# MCU.net
KiCad netlist of a schematic drawn in Altium Designer
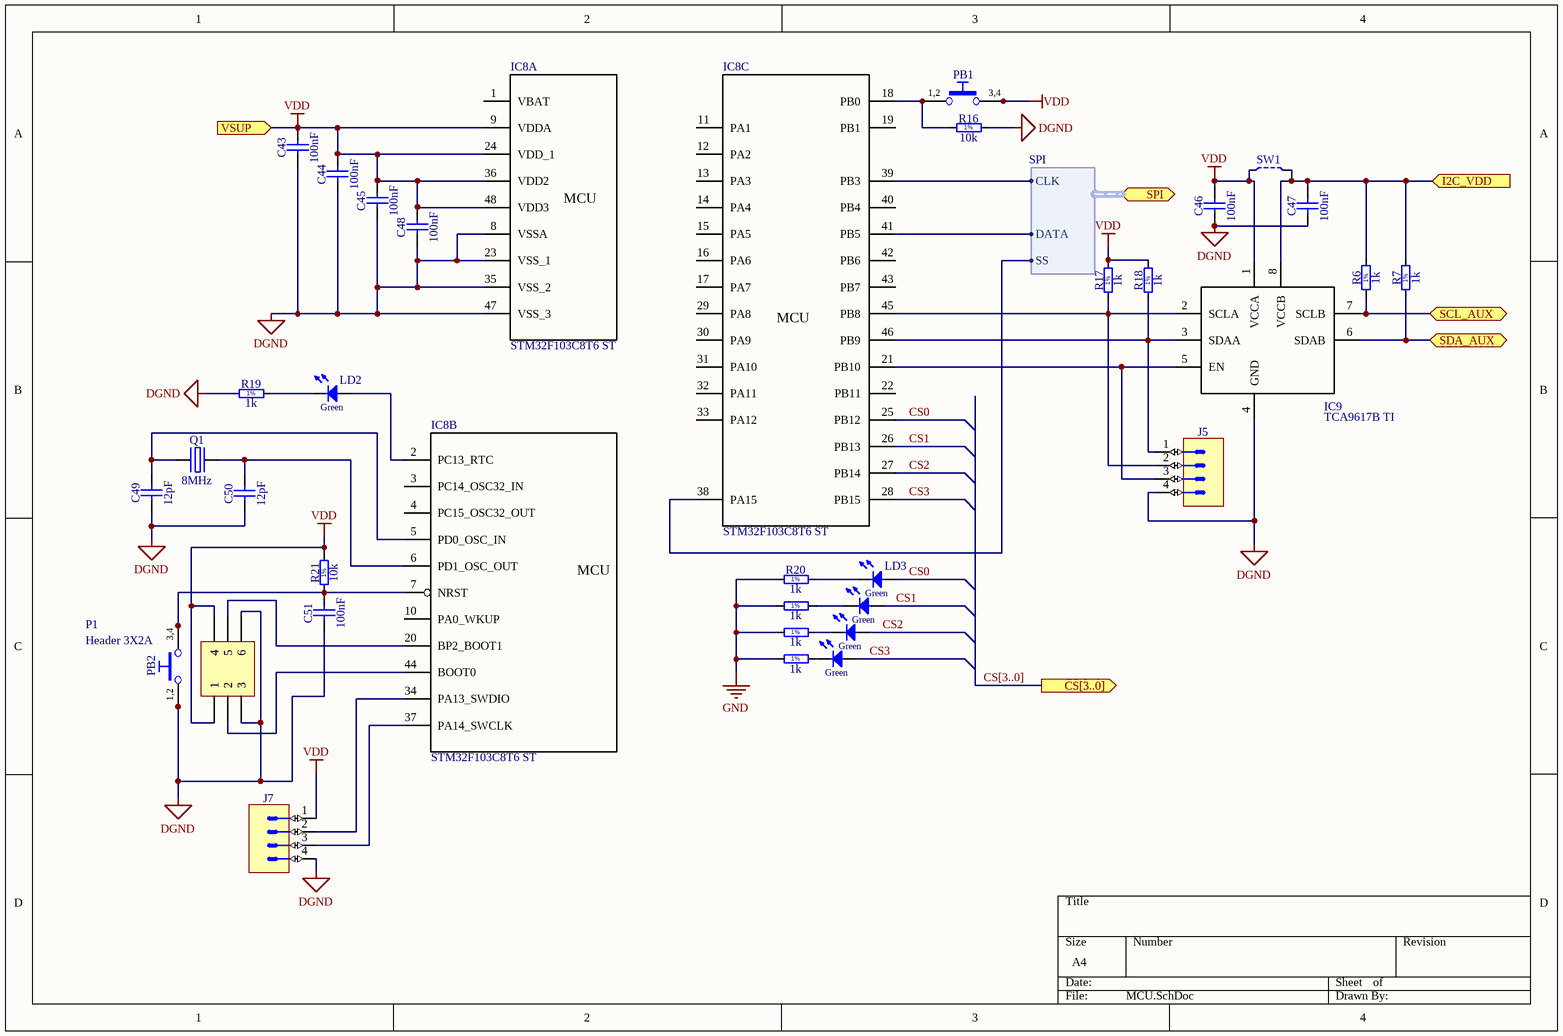
[diagram p0: MCU.SchDoc]

(export (version "E")
  (design (tool "Eeschema 10.0.6"))
  (components
    (comp (ref "C43")
      (value "100nF")
      (footprint "CAPC2012X135N")
      (description "Non-polarised capacitor")
      (fields
        (field (name "PART NUMBER") "CC0805_100NF_50V_10%_X7R")
        (field (name "VOLTAGE") "50V")
        (field (name "AUTHOR") "CERN DEM JLC")
      )
      (libsource (lib "Capacitors") (part "Capacitor - non polarized"))
    )
    (comp (ref "C44")
      (value "100nF")
      (footprint "CAPC2012X135N")
      (description "Non-polarised capacitor")
      (fields
        (field (name "PART NUMBER") "CC0805_100NF_50V_10%_X7R")
        (field (name "VOLTAGE") "50V")
        (field (name "AUTHOR") "CERN DEM JLC")
      )
      (libsource (lib "Capacitors") (part "Capacitor - non polarized"))
    )
    (comp (ref "C45")
      (value "100nF")
      (footprint "CAPC2012X135N")
      (description "Non-polarised capacitor")
      (fields
        (field (name "PART NUMBER") "CC0805_100NF_50V_10%_X7R")
        (field (name "VOLTAGE") "50V")
        (field (name "AUTHOR") "CERN DEM JLC")
      )
      (libsource (lib "Capacitors") (part "Capacitor - non polarized"))
    )
    (comp (ref "C46")
      (value "100nF")
      (footprint "CAPC2012X135N")
      (description "Non-polarised capacitor")
      (fields
        (field (name "PART NUMBER") "CC0805_100NF_50V_10%_X7R")
        (field (name "VOLTAGE") "50V")
        (field (name "AUTHOR") "CERN DEM JLC")
      )
      (libsource (lib "Capacitors") (part "Capacitor - non polarized"))
    )
    (comp (ref "C47")
      (value "100nF")
      (footprint "CAPC2012X135N")
      (description "Non-polarised capacitor")
      (fields
        (field (name "PART NUMBER") "CC0805_100NF_50V_10%_X7R")
        (field (name "VOLTAGE") "50V")
        (field (name "AUTHOR") "CERN DEM JLC")
      )
      (libsource (lib "Capacitors") (part "Capacitor - non polarized"))
    )
    (comp (ref "C48")
      (value "100nF")
      (footprint "CAPC2012X135N")
      (description "Non-polarised capacitor")
      (fields
        (field (name "PART NUMBER") "CC0805_100NF_50V_10%_X7R")
        (field (name "VOLTAGE") "50V")
        (field (name "AUTHOR") "CERN DEM JLC")
      )
      (libsource (lib "Capacitors") (part "Capacitor - non polarized"))
    )
    (comp (ref "C49")
      (value "12pF")
      (footprint "CAPC2012X135N")
      (description "Non-polarised capacitor")
      (fields
        (field (name "PART NUMBER") "CC0805_12PF_50V_5%_NP0")
        (field (name "VOLTAGE") "50V")
        (field (name "AUTHOR") "CERN DEM JLC")
      )
      (libsource (lib "Capacitors") (part "Capacitor - non polarized"))
    )
    (comp (ref "C50")
      (value "12pF")
      (footprint "CAPC2012X135N")
      (description "Non-polarised capacitor")
      (fields
        (field (name "PART NUMBER") "CC0805_12PF_50V_5%_NP0")
        (field (name "VOLTAGE") "50V")
        (field (name "AUTHOR") "CERN DEM JLC")
      )
      (libsource (lib "Capacitors") (part "Capacitor - non polarized"))
    )
    (comp (ref "C51")
      (value "100nF")
      (footprint "CAPC2012X135N")
      (description "Non-polarised capacitor")
      (fields
        (field (name "PART NUMBER") "CC0805_100NF_50V_10%_X7R")
        (field (name "VOLTAGE") "50V")
        (field (name "AUTHOR") "CERN DEM JLC")
      )
      (libsource (lib "Capacitors") (part "Capacitor - non polarized"))
    )
    (comp (ref "IC8")
      (value "STM32F103C8T6 ST")
      (footprint "QFP50P900X900X160-48N")
      (fields (field (name "MANUFACTURER") "ST"))
      (libsource (lib "Additional") (part "STM32F103C8T6"))
    )
    (comp (ref "IC9")
      (value "TCA9617B TI")
      (footprint "TSOP65P490X110-8N")
      (fields (field (name "MANUFACTURER") "TI"))
      (libsource (lib "Additional") (part "TCA9617B"))
    )
    (comp (ref "J5")
      (value "Header 4")
      (footprint "PRECI-DIP_350-V3-104-00-001101")
      (description "Connector 4 Male")
      (fields
        (field (name "PART NUMBER") "PRECI-DIP_350-V3-104-00-001101")
        (field (name "MANUFACTURER") "PRECI-DIP")
        (field (name "AUTHOR") "CERN DEM BC")
      )
      (libsource (lib "") (part "Connector 4 Male_1"))
    )
    (comp (ref "J7")
      (value "Header 4")
      (footprint "PRECI-DIP_350-V3-104-00-001101")
      (description "Connector 4 Male")
      (fields
        (field (name "PART NUMBER") "PRECI-DIP_350-V3-104-00-001101")
        (field (name "MANUFACTURER") "PRECI-DIP")
        (field (name "AUTHOR") "CERN DEM BC")
      )
      (libsource (lib "Connectors") (part "Connector 4 Male"))
    )
    (comp (ref "LD2")
      (value "Green")
      (footprint "LED_OSRAM_LGR971")
      (description "LED Green 1C 2A")
      (fields
        (field (name "PART NUMBER") "LED_OSRAM_LGR971")
        (field (name "MANUFACTURER") "OSRAM")
        (field (name "AUTHOR") "CERN DEM JLC")
      )
      (libsource (lib "ICs And Semiconductors") (part "LED Green 1C 2A"))
    )
    (comp (ref "LD3")
      (value "Green")
      (footprint "LED_OSRAM_LGR971")
      (description "LED Green 1C 2A")
      (fields
        (field (name "PART NUMBER") "LED_OSRAM_LGR971")
        (field (name "MANUFACTURER") "OSRAM")
        (field (name "AUTHOR") "CERN DEM JLC")
      )
      (libsource (lib "ICs And Semiconductors") (part "LED Green 1C 2A"))
    )
    (comp (ref "LD4")
      (value "Green")
      (footprint "LED_OSRAM_LGR971")
      (description "LED Green 1C 2A")
      (fields
        (field (name "PART NUMBER") "LED_OSRAM_LGR971")
        (field (name "MANUFACTURER") "OSRAM")
        (field (name "AUTHOR") "CERN DEM JLC")
      )
      (libsource (lib "ICs And Semiconductors") (part "LED Green 1C 2A"))
    )
    (comp (ref "LD5")
      (value "Green")
      (footprint "LED_OSRAM_LGR971")
      (description "LED Green 1C 2A")
      (fields
        (field (name "PART NUMBER") "LED_OSRAM_LGR971")
        (field (name "MANUFACTURER") "OSRAM")
        (field (name "AUTHOR") "CERN DEM JLC")
      )
      (libsource (lib "ICs And Semiconductors") (part "LED Green 1C 2A"))
    )
    (comp (ref "LD6")
      (value "Green")
      (footprint "LED_OSRAM_LGR971")
      (description "LED Green 1C 2A")
      (fields
        (field (name "PART NUMBER") "LED_OSRAM_LGR971")
        (field (name "MANUFACTURER") "OSRAM")
        (field (name "AUTHOR") "CERN DEM JLC")
      )
      (libsource (lib "ICs And Semiconductors") (part "LED Green 1C 2A"))
    )
    (comp (ref "P1")
      (value "Header 3X2A")
      (footprint "HDR2X3_CEN")
      (description "Header, 3-Pin, Dual row")
      (fields (field (name "PUBLISHER") "Altium Limited"))
      (libsource (lib "Miscellaneous Connectors") (part "Header 3X2A"))
    )
    (comp (ref "PB1")
      (value "Push Button")
      (footprint "PB_OMRON_B3F-1000")
      (description "Push-Button Switch SPDT")
      (fields
        (field (name "PART NUMBER") "PB_OMRON_B3F-1000")
        (field (name "MANUFACTURER") "OMRON")
        (field (name "AUTHOR") "CERN DEM JMW")
      )
      (libsource (lib "") (part "PB SPST 12NO-34NO_1"))
    )
    (comp (ref "PB2")
      (value "Push Button")
      (footprint "PB_OMRON_B3F-1000")
      (description "Push-Button Switch SPDT")
      (fields
        (field (name "PART NUMBER") "PB_OMRON_B3F-1000")
        (field (name "MANUFACTURER") "OMRON")
        (field (name "AUTHOR") "CERN DEM JMW")
      )
      (libsource (lib "Eletro-mechanical") (part "PB SPST 12NO-34NO"))
    )
    (comp (ref "Q1")
      (value "8MHz")
      (footprint "XTAL_TXC_7A")
      (description "Quartz Crystal")
      (fields
        (field (name "PART NUMBER") "XTAL_8MHZ_TXC_7A-8.000MAAE-T")
        (field (name "MANUFACTURER") "TXC CORPORATION")
        (field (name "AUTHOR") "CERN DEM JLC")
      )
      (libsource (lib "ICs And Semiconductors") (part "Quartz Crystal"))
    )
    (comp (ref "R6")
      (value "1k")
      (footprint "RESC2012X60N")
      (description "Resistor - 1%")
      (fields
        (field (name "PART NUMBER") "R0805_1K_1%_0.125W_100PPM")
        (field (name "POWER") "0.125W")
        (field (name "AUTHOR") "CERN DEM JLC")
      )
      (libsource (lib "Resistors") (part "Resistor - 1%"))
    )
    (comp (ref "R7")
      (value "1k")
      (footprint "RESC2012X60N")
      (description "Resistor - 1%")
      (fields
        (field (name "PART NUMBER") "R0805_1K_1%_0.125W_100PPM")
        (field (name "POWER") "0.125W")
        (field (name "AUTHOR") "CERN DEM JLC")
      )
      (libsource (lib "Resistors") (part "Resistor - 1%"))
    )
    (comp (ref "R16")
      (value "10k")
      (footprint "RESC2012X60N")
      (description "Resistor - 1%")
      (fields
        (field (name "PART NUMBER") "R0805_10K_1%_0.125W_100PPM")
        (field (name "POWER") "0.125W")
        (field (name "AUTHOR") "CERN DEM JLC")
      )
      (libsource (lib "Resistors") (part "Resistor - 1%"))
    )
    (comp (ref "R17")
      (value "1k")
      (footprint "RESC2012X60N")
      (description "Resistor - 1%")
      (fields
        (field (name "PART NUMBER") "R0805_1K_1%_0.125W_100PPM")
        (field (name "POWER") "0.125W")
        (field (name "AUTHOR") "CERN DEM JLC")
      )
      (libsource (lib "Resistors") (part "Resistor - 1%"))
    )
    (comp (ref "R18")
      (value "1k")
      (footprint "RESC2012X60N")
      (description "Resistor - 1%")
      (fields
        (field (name "PART NUMBER") "R0805_1K_1%_0.125W_100PPM")
        (field (name "POWER") "0.125W")
        (field (name "AUTHOR") "CERN DEM JLC")
      )
      (libsource (lib "Resistors") (part "Resistor - 1%"))
    )
    (comp (ref "R19")
      (value "1k")
      (footprint "RESC2012X60N")
      (description "Resistor - 1%")
      (fields
        (field (name "PART NUMBER") "R0805_1K_1%_0.125W_100PPM")
        (field (name "POWER") "0.125W")
        (field (name "AUTHOR") "CERN DEM JLC")
      )
      (libsource (lib "Resistors") (part "Resistor - 1%"))
    )
    (comp (ref "R20")
      (value "1k")
      (footprint "RESC2012X60N")
      (description "Resistor - 1%")
      (fields
        (field (name "PART NUMBER") "R0805_1K_1%_0.125W_100PPM")
        (field (name "POWER") "0.125W")
        (field (name "AUTHOR") "CERN DEM JLC")
      )
      (libsource (lib "Resistors") (part "Resistor - 1%"))
    )
    (comp (ref "R21")
      (value "10k")
      (footprint "RESC2012X60N")
      (description "Resistor - 1%")
      (fields
        (field (name "PART NUMBER") "R0805_10K_1%_0.125W_100PPM")
        (field (name "POWER") "0.125W")
        (field (name "AUTHOR") "CERN DEM JLC")
      )
      (libsource (lib "Resistors") (part "Resistor - 1%"))
    )
    (comp (ref "R22")
      (value "1k")
      (footprint "RESC2012X60N")
      (description "Resistor - 1%")
      (fields
        (field (name "PART NUMBER") "R0805_1K_1%_0.125W_100PPM")
        (field (name "POWER") "0.125W")
        (field (name "AUTHOR") "CERN DEM JLC")
      )
      (libsource (lib "Resistors") (part "Resistor - 1%"))
    )
    (comp (ref "R23")
      (value "1k")
      (footprint "RESC2012X60N")
      (description "Resistor - 1%")
      (fields
        (field (name "PART NUMBER") "R0805_1K_1%_0.125W_100PPM")
        (field (name "POWER") "0.125W")
        (field (name "AUTHOR") "CERN DEM JLC")
      )
      (libsource (lib "Resistors") (part "Resistor - 1%"))
    )
    (comp (ref "R24")
      (value "1k")
      (footprint "RESC2012X60N")
      (description "Resistor - 1%")
      (fields
        (field (name "PART NUMBER") "R0805_1K_1%_0.125W_100PPM")
        (field (name "POWER") "0.125W")
        (field (name "AUTHOR") "CERN DEM JLC")
      )
      (libsource (lib "Resistors") (part "Resistor - 1%"))
    )
    (comp (ref "SW1")
      (value "Switch")
      (footprint "JUMPSMD0805_G50")
      (description "2 SMD Pads for Bound by Solder  Drop")
      (fields
        (field (name "PART NUMBER") "JUMPSMD0805_G50")
        (field (name "MANUFACTURER") "None")
        (field (name "AUTHOR") "CERN DEM JLC")
      )
      (libsource (lib "Eletro-mechanical") (part "SMD Solder Jumper"))
    )
  )
  (nets
    (net (code "2") (name "/CLK") (class "Default")
      (node (ref "IC8") (pin "39") (pinfunction "PB3_39") (pintype "passive"))
    )
    (net (code "3") (name "/CS0") (class "Default")
      (node (ref "IC8") (pin "25") (pinfunction "PB12_25") (pintype "passive"))
      (node (ref "LD3") (pin "2") (pinfunction "A_2") (pintype "passive"))
    )
    (net (code "4") (name "/CS1") (class "Default")
      (node (ref "IC8") (pin "26") (pinfunction "PB13_26") (pintype "passive"))
      (node (ref "LD4") (pin "2") (pinfunction "A_2") (pintype "passive"))
    )
    (net (code "5") (name "/CS2") (class "Default")
      (node (ref "IC8") (pin "27") (pinfunction "PB14_27") (pintype "passive"))
      (node (ref "LD5") (pin "2") (pinfunction "A_2") (pintype "passive"))
    )
    (net (code "6") (name "/CS3") (class "Default")
      (node (ref "IC8") (pin "28") (pinfunction "PB15_28") (pintype "passive"))
      (node (ref "LD6") (pin "2") (pinfunction "A_2") (pintype "passive"))
    )
    (net (code "8") (name "/DATA") (class "Default")
      (node (ref "IC8") (pin "41") (pinfunction "PB5_41") (pintype "passive"))
    )
    (net (code "9") (name "/I2C_VDD") (class "Default")
      (node (ref "C47") (pin "2") (pinfunction "2_2") (pintype "passive"))
      (node (ref "IC9") (pin "8") (pinfunction "VCCB_8") (pintype "passive"))
      (node (ref "R6") (pin "2") (pinfunction "2_2") (pintype "passive"))
      (node (ref "R7") (pin "2") (pinfunction "2_2") (pintype "passive"))
      (node (ref "SW1") (pin "2") (pinfunction "2_2") (pintype "passive"))
    )
    (net (code "10") (name "/SCL_AUX") (class "Default")
      (node (ref "IC9") (pin "7") (pinfunction "SCLB_7") (pintype "passive"))
      (node (ref "R6") (pin "1") (pinfunction "1_1") (pintype "passive"))
    )
    (net (code "11") (name "/SDA_AUX") (class "Default")
      (node (ref "IC9") (pin "6") (pinfunction "SDAB_6") (pintype "passive"))
      (node (ref "R7") (pin "1") (pinfunction "1_1") (pintype "passive"))
    )
    (net (code "12") (name "/SS") (class "Default")
      (node (ref "IC8") (pin "38") (pinfunction "PA15_38") (pintype "passive"))
    )
    (net (code "14") (name "DGND") (class "Default")
      (node (ref "C43") (pin "1") (pinfunction "1_1") (pintype "passive"))
      (node (ref "C44") (pin "1") (pinfunction "1_1") (pintype "passive"))
      (node (ref "C45") (pin "1") (pinfunction "1_1") (pintype "passive"))
      (node (ref "C46") (pin "1") (pinfunction "1_1") (pintype "passive"))
      (node (ref "C47") (pin "1") (pinfunction "1_1") (pintype "passive"))
      (node (ref "C48") (pin "1") (pinfunction "1_1") (pintype "passive"))
      (node (ref "C49") (pin "1") (pinfunction "1_1") (pintype "passive"))
      (node (ref "C50") (pin "1") (pinfunction "1_1") (pintype "passive"))
      (node (ref "C51") (pin "1") (pinfunction "1_1") (pintype "passive"))
      (node (ref "IC8") (pin "23") (pinfunction "VSS_1_23") (pintype "passive"))
      (node (ref "IC8") (pin "35") (pinfunction "VSS_2_35") (pintype "passive"))
      (node (ref "IC8") (pin "47") (pinfunction "VSS_3_47") (pintype "passive"))
      (node (ref "IC8") (pin "8") (pinfunction "VSSA_8") (pintype "passive"))
      (node (ref "IC9") (pin "4") (pinfunction "GND_4") (pintype "passive"))
      (node (ref "J5") (pin "4") (pinfunction "4_4") (pintype "bidirectional"))
      (node (ref "J7") (pin "4") (pinfunction "4_4") (pintype "bidirectional"))
      (node (ref "P1") (pin "3") (pinfunction "3_3") (pintype "passive"))
      (node (ref "P1") (pin "6") (pinfunction "6_6") (pintype "passive"))
      (node (ref "PB2") (pin "1") (pinfunction "1_1") (pintype "passive"))
      (node (ref "PB2") (pin "2") (pinfunction "2_2") (pintype "passive"))
      (node (ref "R16") (pin "2") (pinfunction "2_2") (pintype "passive"))
      (node (ref "R19") (pin "1") (pinfunction "1_1") (pintype "passive"))
    )
    (net (code "15") (name "GND") (class "Default")
      (node (ref "R20") (pin "1") (pinfunction "1_1") (pintype "passive"))
      (node (ref "R22") (pin "1") (pinfunction "1_1") (pintype "passive"))
      (node (ref "R23") (pin "1") (pinfunction "1_1") (pintype "passive"))
      (node (ref "R24") (pin "1") (pinfunction "1_1") (pintype "passive"))
    )
    (net (code "16") (name "Net-(IC8B-BOOT0)") (class "Default")
      (node (ref "IC8") (pin "44") (pinfunction "BOOT0_44") (pintype "passive"))
      (node (ref "P1") (pin "2") (pinfunction "2_2") (pintype "passive"))
    )
    (net (code "17") (name "Net-(IC8B-BP2_BOOT1)") (class "Default")
      (node (ref "IC8") (pin "20") (pinfunction "BP2_BOOT1_20") (pintype "passive"))
      (node (ref "P1") (pin "5") (pinfunction "5_5") (pintype "passive"))
    )
    (net (code "18") (name "Net-(IC8B-NRST)") (class "Default")
      (node (ref "C51") (pin "2") (pinfunction "2_2") (pintype "passive"))
      (node (ref "IC8") (pin "7") (pinfunction "NRST_7") (pintype "passive"))
      (node (ref "PB2") (pin "3") (pinfunction "3_3") (pintype "passive"))
      (node (ref "PB2") (pin "4") (pinfunction "4_4") (pintype "passive"))
      (node (ref "R21") (pin "1") (pinfunction "1_1") (pintype "passive"))
    )
    (net (code "19") (name "Net-(IC8B-PA13_SWDIO)") (class "Default")
      (node (ref "IC8") (pin "34") (pinfunction "PA13_SWDIO_34") (pintype "passive"))
      (node (ref "J7") (pin "2") (pinfunction "2_2") (pintype "bidirectional"))
    )
    (net (code "20") (name "Net-(IC8B-PA14_SWCLK)") (class "Default")
      (node (ref "IC8") (pin "37") (pinfunction "PA14_SWCLK_37") (pintype "passive"))
      (node (ref "J7") (pin "3") (pinfunction "3_3") (pintype "bidirectional"))
    )
    (net (code "21") (name "Net-(IC8B-PC13_RTC)") (class "Default")
      (node (ref "IC8") (pin "2") (pinfunction "PC13_RTC_2") (pintype "passive"))
      (node (ref "LD2") (pin "2") (pinfunction "A_2") (pintype "passive"))
    )
    (net (code "22") (name "Net-(IC8B-PD0_OSC_IN)") (class "Default")
      (node (ref "C49") (pin "2") (pinfunction "2_2") (pintype "passive"))
      (node (ref "IC8") (pin "5") (pinfunction "PD0_OSC_IN_5") (pintype "passive"))
      (node (ref "Q1") (pin "1") (pinfunction "OSC1_1") (pintype "passive"))
    )
    (net (code "23") (name "Net-(IC8B-PD1_OSC_OUT)") (class "Default")
      (node (ref "C50") (pin "2") (pinfunction "2_2") (pintype "passive"))
      (node (ref "IC8") (pin "6") (pinfunction "PD1_OSC_OUT_6") (pintype "passive"))
      (node (ref "Q1") (pin "2") (pinfunction "OSC2_2") (pintype "passive"))
    )
    (net (code "24") (name "Net-(IC8C-PB0)") (class "Default")
      (node (ref "IC8") (pin "18") (pinfunction "PB0_18") (pintype "passive"))
      (node (ref "PB1") (pin "1") (pinfunction "1_1") (pintype "passive"))
      (node (ref "PB1") (pin "2") (pinfunction "2_2") (pintype "passive"))
      (node (ref "R16") (pin "1") (pinfunction "1_1") (pintype "passive"))
    )
    (net (code "25") (name "Net-(IC8C-PB8)") (class "Default")
      (node (ref "IC8") (pin "45") (pinfunction "PB8_45") (pintype "passive"))
      (node (ref "IC9") (pin "2") (pinfunction "SCLA_2") (pintype "passive"))
      (node (ref "J5") (pin "2") (pinfunction "2_2") (pintype "bidirectional"))
      (node (ref "R17") (pin "1") (pinfunction "1_1") (pintype "passive"))
    )
    (net (code "26") (name "Net-(IC8C-PB9)") (class "Default")
      (node (ref "IC8") (pin "46") (pinfunction "PB9_46") (pintype "passive"))
      (node (ref "IC9") (pin "3") (pinfunction "SDAA_3") (pintype "passive"))
      (node (ref "J5") (pin "1") (pinfunction "1_1") (pintype "bidirectional"))
      (node (ref "R18") (pin "1") (pinfunction "1_1") (pintype "passive"))
    )
    (net (code "27") (name "Net-(IC8C-PB10)") (class "Default")
      (node (ref "IC8") (pin "21") (pinfunction "PB10_21") (pintype "passive"))
      (node (ref "IC9") (pin "5") (pinfunction "EN_5") (pintype "passive"))
      (node (ref "J5") (pin "3") (pinfunction "3_3") (pintype "bidirectional"))
    )
    (net (code "28") (name "Net-(LD2-C)") (class "Default")
      (node (ref "LD2") (pin "1") (pinfunction "C_1") (pintype "passive"))
      (node (ref "R19") (pin "2") (pinfunction "2_2") (pintype "passive"))
    )
    (net (code "29") (name "Net-(LD3-C)") (class "Default")
      (node (ref "LD3") (pin "1") (pinfunction "C_1") (pintype "passive"))
      (node (ref "R20") (pin "2") (pinfunction "2_2") (pintype "passive"))
    )
    (net (code "30") (name "Net-(LD4-C)") (class "Default")
      (node (ref "LD4") (pin "1") (pinfunction "C_1") (pintype "passive"))
      (node (ref "R22") (pin "2") (pinfunction "2_2") (pintype "passive"))
    )
    (net (code "31") (name "Net-(LD5-C)") (class "Default")
      (node (ref "LD5") (pin "1") (pinfunction "C_1") (pintype "passive"))
      (node (ref "R23") (pin "2") (pinfunction "2_2") (pintype "passive"))
    )
    (net (code "32") (name "Net-(LD6-C)") (class "Default")
      (node (ref "LD6") (pin "1") (pinfunction "C_1") (pintype "passive"))
      (node (ref "R24") (pin "2") (pinfunction "2_2") (pintype "passive"))
    )
    (net (code "33") (name "VDD") (class "Default")
      (node (ref "C43") (pin "2") (pinfunction "2_2") (pintype "passive"))
      (node (ref "C44") (pin "2") (pinfunction "2_2") (pintype "passive"))
      (node (ref "C45") (pin "2") (pinfunction "2_2") (pintype "passive"))
      (node (ref "C46") (pin "2") (pinfunction "2_2") (pintype "passive"))
      (node (ref "C48") (pin "2") (pinfunction "2_2") (pintype "passive"))
      (node (ref "IC8") (pin "24") (pinfunction "VDD_1_24") (pintype "passive"))
      (node (ref "IC8") (pin "36") (pinfunction "VDD2_36") (pintype "passive"))
      (node (ref "IC8") (pin "48") (pinfunction "VDD3_48") (pintype "passive"))
      (node (ref "IC8") (pin "9") (pinfunction "VDDA_9") (pintype "passive"))
      (node (ref "IC9") (pin "1") (pinfunction "VCCA_1") (pintype "passive"))
      (node (ref "J7") (pin "1") (pinfunction "1_1") (pintype "bidirectional"))
      (node (ref "P1") (pin "1") (pinfunction "1_1") (pintype "passive"))
      (node (ref "P1") (pin "4") (pinfunction "4_4") (pintype "passive"))
      (node (ref "PB1") (pin "3") (pinfunction "3_3") (pintype "passive"))
      (node (ref "PB1") (pin "4") (pinfunction "4_4") (pintype "passive"))
      (node (ref "R17") (pin "2") (pinfunction "2_2") (pintype "passive"))
      (node (ref "R18") (pin "2") (pinfunction "2_2") (pintype "passive"))
      (node (ref "R21") (pin "2") (pinfunction "2_2") (pintype "passive"))
      (node (ref "SW1") (pin "1") (pinfunction "1_1") (pintype "passive"))
    )
    (net (code "34") (name "unconnected-(IC8A-VBAT-Pad1)") (class "Default")
      (node (ref "IC8") (pin "1") (pinfunction "VBAT_1") (pintype "passive"))
    )
    (net (code "35") (name "unconnected-(IC8B-PA0_WKUP-Pad10)") (class "Default")
      (node (ref "IC8") (pin "10") (pinfunction "PA0_WKUP_10") (pintype "passive"))
    )
    (net (code "36") (name "unconnected-(IC8B-PC14_OSC32_IN-Pad3)") (class "Default")
      (node (ref "IC8") (pin "3") (pinfunction "PC14_OSC32_IN_3") (pintype "passive"))
    )
    (net (code "37") (name "unconnected-(IC8B-PC15_OSC32_OUT-Pad4)") (class "Default")
      (node (ref "IC8") (pin "4") (pinfunction "PC15_OSC32_OUT_4") (pintype "passive"))
    )
    (net (code "38") (name "unconnected-(IC8C-PA1-Pad11)") (class "Default")
      (node (ref "IC8") (pin "11") (pinfunction "PA1_11") (pintype "passive"))
    )
    (net (code "39") (name "unconnected-(IC8C-PA2-Pad12)") (class "Default")
      (node (ref "IC8") (pin "12") (pinfunction "PA2_12") (pintype "passive"))
    )
    (net (code "40") (name "unconnected-(IC8C-PA3-Pad13)") (class "Default")
      (node (ref "IC8") (pin "13") (pinfunction "PA3_13") (pintype "passive"))
    )
    (net (code "41") (name "unconnected-(IC8C-PA4-Pad14)") (class "Default")
      (node (ref "IC8") (pin "14") (pinfunction "PA4_14") (pintype "passive"))
    )
    (net (code "42") (name "unconnected-(IC8C-PA5-Pad15)") (class "Default")
      (node (ref "IC8") (pin "15") (pinfunction "PA5_15") (pintype "passive"))
    )
    (net (code "43") (name "unconnected-(IC8C-PA6-Pad16)") (class "Default")
      (node (ref "IC8") (pin "16") (pinfunction "PA6_16") (pintype "passive"))
    )
    (net (code "44") (name "unconnected-(IC8C-PA7-Pad17)") (class "Default")
      (node (ref "IC8") (pin "17") (pinfunction "PA7_17") (pintype "passive"))
    )
    (net (code "45") (name "unconnected-(IC8C-PA8-Pad29)") (class "Default")
      (node (ref "IC8") (pin "29") (pinfunction "PA8_29") (pintype "passive"))
    )
    (net (code "46") (name "unconnected-(IC8C-PA9-Pad30)") (class "Default")
      (node (ref "IC8") (pin "30") (pinfunction "PA9_30") (pintype "passive"))
    )
    (net (code "47") (name "unconnected-(IC8C-PA10-Pad31)") (class "Default")
      (node (ref "IC8") (pin "31") (pinfunction "PA10_31") (pintype "passive"))
    )
    (net (code "48") (name "unconnected-(IC8C-PA11-Pad32)") (class "Default")
      (node (ref "IC8") (pin "32") (pinfunction "PA11_32") (pintype "passive"))
    )
    (net (code "49") (name "unconnected-(IC8C-PA12-Pad33)") (class "Default")
      (node (ref "IC8") (pin "33") (pinfunction "PA12_33") (pintype "passive"))
    )
    (net (code "50") (name "unconnected-(IC8C-PB1-Pad19)") (class "Default")
      (node (ref "IC8") (pin "19") (pinfunction "PB1_19") (pintype "passive"))
    )
    (net (code "51") (name "unconnected-(IC8C-PB4-Pad40)") (class "Default")
      (node (ref "IC8") (pin "40") (pinfunction "PB4_40") (pintype "passive"))
    )
    (net (code "52") (name "unconnected-(IC8C-PB6-Pad42)") (class "Default")
      (node (ref "IC8") (pin "42") (pinfunction "PB6_42") (pintype "passive"))
    )
    (net (code "53") (name "unconnected-(IC8C-PB7-Pad43)") (class "Default")
      (node (ref "IC8") (pin "43") (pinfunction "PB7_43") (pintype "passive"))
    )
    (net (code "54") (name "unconnected-(IC8C-PB11-Pad22)") (class "Default")
      (node (ref "IC8") (pin "22") (pinfunction "PB11_22") (pintype "passive"))
    )
  )
)
